# LowVBoard_01.net
KiCad netlist of a schematic drawn in EAGLE
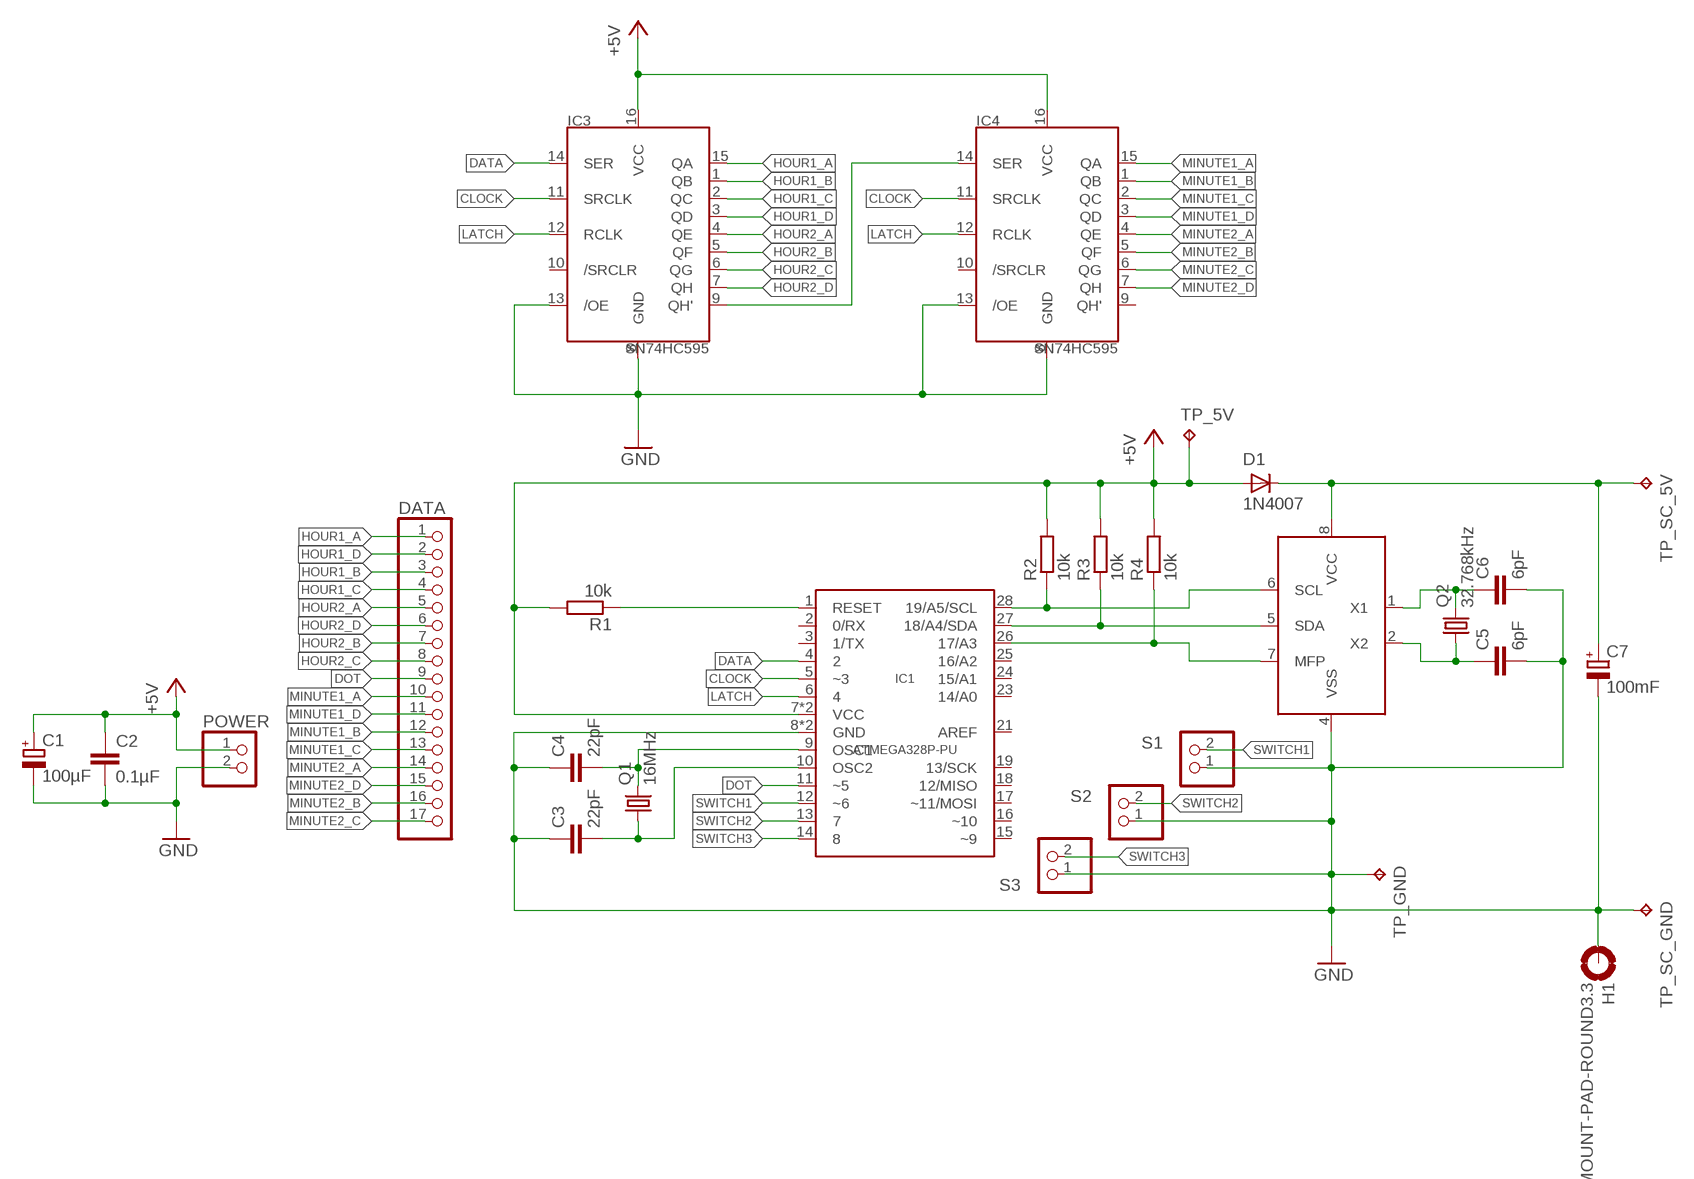
[diagram p0: schematic, sheet 1]

(export (version "E")
  (design (tool "Eeschema 10.0.6"))
  (components
    (comp (ref "C1")
      (value "100µF")
      (footprint "eagle-import:E2-5")
      (libsource (lib "eagle-import") (part "CPOL-EUE2-5"))
    )
    (comp (ref "C2")
      (value "0.1µF")
      (footprint "eagle-import:C025-024X044")
      (libsource (lib "eagle-import") (part "C-EU025-024X044"))
    )
    (comp (ref "C3")
      (value "22pF")
      (footprint "eagle-import:C025-024X044")
      (libsource (lib "eagle-import") (part "C-EU025-024X044"))
    )
    (comp (ref "C4")
      (value "22pF")
      (footprint "eagle-import:C025-024X044")
      (libsource (lib "eagle-import") (part "C-EU025-024X044"))
    )
    (comp (ref "C5")
      (value "6pF")
      (footprint "eagle-import:C025-024X044")
      (libsource (lib "eagle-import") (part "C-EU025-024X044"))
    )
    (comp (ref "C6")
      (value "6pF")
      (footprint "eagle-import:C025-024X044")
      (libsource (lib "eagle-import") (part "C-EU025-024X044"))
    )
    (comp (ref "C7")
      (value "100mF")
      (footprint "eagle-import:SUPERCAP-11.5")
      (libsource (lib "eagle-import") (part "FTW0H104ZF"))
    )
    (comp (ref "D1")
      (value "1N4007")
      (footprint "eagle-import:DO41-7.6")
      (libsource (lib "eagle-import") (part "1N4007"))
    )
    (comp (ref "DATA")
      (value "PINHD-1X17")
      (footprint "eagle-import:1X17")
      (libsource (lib "eagle-import") (part "PINHD-1X17"))
    )
    (comp (ref "H1")
      (value "MOUNT-PAD-ROUND3.3")
      (footprint "eagle-import:3,3-PAD")
      (libsource (lib "eagle-import") (part "MOUNT-PAD-ROUND3.3"))
    )
    (comp (ref "IC1")
      (value "ATMEGA328P-PU")
      (footprint "eagle-import:DIP28")
      (libsource (lib "eagle-import") (part "ATMEGA328P-PU"))
    )
    (comp (ref "IC2")
      (value "MCP7940M")
      (footprint "eagle-import:DIL8")
      (libsource (lib "eagle-import") (part "MCP7940M-I/P"))
    )
    (comp (ref "IC3")
      (value "SN74HC595")
      (footprint "eagle-import:DIL16")
      (libsource (lib "eagle-import") (part "SN74HC595"))
    )
    (comp (ref "IC4")
      (value "SN74HC595")
      (footprint "eagle-import:DIL16")
      (libsource (lib "eagle-import") (part "SN74HC595"))
    )
    (comp (ref "POWER")
      (value "PINHD-1X2")
      (footprint "eagle-import:1X02")
      (libsource (lib "eagle-import") (part "PINHD-1X2"))
    )
    (comp (ref "Q1")
      (value "16MHz")
      (footprint "eagle-import:HC49_S")
      (libsource (lib "eagle-import") (part "CRYSTALHC49S"))
    )
    (comp (ref "Q2")
      (value "32.768kHz")
      (footprint "eagle-import:CFS-206")
      (libsource (lib "eagle-import") (part "CFS-206"))
    )
    (comp (ref "R1")
      (value "10k")
      (footprint "eagle-import:0207_7")
      (libsource (lib "eagle-import") (part "R-EU_0207/7"))
    )
    (comp (ref "R2")
      (value "10k")
      (footprint "eagle-import:0207_7")
      (libsource (lib "eagle-import") (part "R-EU_0207/7"))
    )
    (comp (ref "R3")
      (value "10k")
      (footprint "eagle-import:0207_7")
      (libsource (lib "eagle-import") (part "R-EU_0207/7"))
    )
    (comp (ref "R4")
      (value "10k")
      (footprint "eagle-import:0207_7")
      (libsource (lib "eagle-import") (part "R-EU_0207/7"))
    )
    (comp (ref "S1")
      (value "PINHD-1X2/90")
      (footprint "eagle-import:1X02_90")
      (libsource (lib "eagle-import") (part "PINHD-1X2/90"))
    )
    (comp (ref "S2")
      (value "PINHD-1X2/90")
      (footprint "eagle-import:1X02_90")
      (libsource (lib "eagle-import") (part "PINHD-1X2/90"))
    )
    (comp (ref "S3")
      (value "PINHD-1X2/90")
      (footprint "eagle-import:1X02_90")
      (libsource (lib "eagle-import") (part "PINHD-1X2/90"))
    )
    (comp (ref "TP_5V")
      (value "TPPAD1-13")
      (footprint "eagle-import:P1-13")
      (libsource (lib "eagle-import") (part "TPPAD1-13"))
    )
    (comp (ref "TP_GND")
      (value "TPPAD1-13")
      (footprint "eagle-import:P1-13")
      (libsource (lib "eagle-import") (part "TPPAD1-13"))
    )
    (comp (ref "TP_SC_5V")
      (value "TPPAD1-13")
      (footprint "eagle-import:P1-13")
      (libsource (lib "eagle-import") (part "TPPAD1-13"))
    )
    (comp (ref "TP_SC_GND")
      (value "TPPAD1-13")
      (footprint "eagle-import:P1-13")
      (libsource (lib "eagle-import") (part "TPPAD1-13"))
    )
  )
  (nets
    (net (code "1") (name "+5V") (class "Default")
      (node (ref "C1") (pin "+") (pinfunction "+_+") (pintype "passive"))
      (node (ref "C2") (pin "1") (pinfunction "1_1") (pintype "passive"))
      (node (ref "D1") (pin "A") (pinfunction "A_A") (pintype "passive"))
      (node (ref "IC1") (pin "20") (pinfunction "VCC_20") (pintype "bidirectional"))
      (node (ref "IC1") (pin "7") (pinfunction "VCC_7") (pintype "bidirectional"))
      (node (ref "IC3") (pin "16") (pinfunction "VCC_16") (pintype "bidirectional"))
      (node (ref "IC4") (pin "16") (pinfunction "VCC_16") (pintype "bidirectional"))
      (node (ref "POWER") (pin "1") (pinfunction "1_1") (pintype "passive"))
      (node (ref "R1") (pin "2") (pinfunction "2_2") (pintype "passive"))
      (node (ref "R2") (pin "2") (pinfunction "2_2") (pintype "passive"))
      (node (ref "R3") (pin "2") (pinfunction "2_2") (pintype "passive"))
      (node (ref "R4") (pin "2") (pinfunction "2_2") (pintype "passive"))
      (node (ref "TP_5V") (pin "TP") (pinfunction "TP_TP") (pintype "input"))
    )
    (net (code "2") (name "CLOCK") (class "Default")
      (node (ref "IC1") (pin "5") (pinfunction "~{3}_5") (pintype "bidirectional"))
      (node (ref "IC3") (pin "11") (pinfunction "SRCLK_11") (pintype "bidirectional"))
      (node (ref "IC4") (pin "11") (pinfunction "SRCLK_11") (pintype "bidirectional"))
    )
    (net (code "3") (name "DATA") (class "Default")
      (node (ref "IC1") (pin "4") (pinfunction "2_4") (pintype "bidirectional"))
      (node (ref "IC3") (pin "14") (pinfunction "SER_14") (pintype "bidirectional"))
    )
    (net (code "4") (name "DOT") (class "Default")
      (node (ref "DATA") (pin "9") (pinfunction "9_9") (pintype "passive"))
      (node (ref "IC1") (pin "11") (pinfunction "~{5}_11") (pintype "bidirectional"))
    )
    (net (code "5") (name "GND") (class "Default")
      (node (ref "C1") (pin "-") (pinfunction "-_-") (pintype "passive"))
      (node (ref "C2") (pin "2") (pinfunction "2_2") (pintype "passive"))
      (node (ref "C3") (pin "1") (pinfunction "1_1") (pintype "passive"))
      (node (ref "C4") (pin "1") (pinfunction "1_1") (pintype "passive"))
      (node (ref "C5") (pin "2") (pinfunction "2_2") (pintype "passive"))
      (node (ref "C6") (pin "2") (pinfunction "2_2") (pintype "passive"))
      (node (ref "C7") (pin "-") (pinfunction "-_-") (pintype "passive"))
      (node (ref "H1") (pin "B3,3") (pinfunction "MOUNT_B3,3") (pintype "passive"))
      (node (ref "IC1") (pin "22") (pinfunction "GND_22") (pintype "bidirectional"))
      (node (ref "IC1") (pin "8") (pinfunction "GND_8") (pintype "bidirectional"))
      (node (ref "IC2") (pin "4") (pinfunction "VSS_4") (pintype "bidirectional"))
      (node (ref "IC3") (pin "13") (pinfunction "/OE_13") (pintype "bidirectional"))
      (node (ref "IC3") (pin "8") (pinfunction "GND_8") (pintype "bidirectional"))
      (node (ref "IC4") (pin "13") (pinfunction "/OE_13") (pintype "bidirectional"))
      (node (ref "IC4") (pin "8") (pinfunction "GND_8") (pintype "bidirectional"))
      (node (ref "POWER") (pin "2") (pinfunction "2_2") (pintype "passive"))
      (node (ref "S1") (pin "1") (pinfunction "1_1") (pintype "passive"))
      (node (ref "S2") (pin "1") (pinfunction "1_1") (pintype "passive"))
      (node (ref "S3") (pin "1") (pinfunction "1_1") (pintype "passive"))
      (node (ref "TP_GND") (pin "TP") (pinfunction "TP_TP") (pintype "input"))
      (node (ref "TP_SC_GND") (pin "TP") (pinfunction "TP_TP") (pintype "input"))
    )
    (net (code "6") (name "HOUR1_A") (class "Default")
      (node (ref "DATA") (pin "1") (pinfunction "1_1") (pintype "passive"))
      (node (ref "IC3") (pin "15") (pinfunction "QA_15") (pintype "bidirectional"))
    )
    (net (code "7") (name "HOUR1_B") (class "Default")
      (node (ref "DATA") (pin "3") (pinfunction "3_3") (pintype "passive"))
      (node (ref "IC3") (pin "1") (pinfunction "QB_1") (pintype "bidirectional"))
    )
    (net (code "8") (name "HOUR1_C") (class "Default")
      (node (ref "DATA") (pin "4") (pinfunction "4_4") (pintype "passive"))
      (node (ref "IC3") (pin "2") (pinfunction "QC_2") (pintype "bidirectional"))
    )
    (net (code "9") (name "HOUR1_D") (class "Default")
      (node (ref "DATA") (pin "2") (pinfunction "2_2") (pintype "passive"))
      (node (ref "IC3") (pin "3") (pinfunction "QD_3") (pintype "bidirectional"))
    )
    (net (code "10") (name "HOUR2_A") (class "Default")
      (node (ref "DATA") (pin "5") (pinfunction "5_5") (pintype "passive"))
      (node (ref "IC3") (pin "4") (pinfunction "QE_4") (pintype "bidirectional"))
    )
    (net (code "11") (name "HOUR2_B") (class "Default")
      (node (ref "DATA") (pin "7") (pinfunction "7_7") (pintype "passive"))
      (node (ref "IC3") (pin "5") (pinfunction "QF_5") (pintype "bidirectional"))
    )
    (net (code "12") (name "HOUR2_C") (class "Default")
      (node (ref "DATA") (pin "8") (pinfunction "8_8") (pintype "passive"))
      (node (ref "IC3") (pin "6") (pinfunction "QG_6") (pintype "bidirectional"))
    )
    (net (code "13") (name "HOUR2_D") (class "Default")
      (node (ref "DATA") (pin "6") (pinfunction "6_6") (pintype "passive"))
      (node (ref "IC3") (pin "7") (pinfunction "QH_7") (pintype "bidirectional"))
    )
    (net (code "14") (name "LATCH") (class "Default")
      (node (ref "IC1") (pin "6") (pinfunction "4_6") (pintype "bidirectional"))
      (node (ref "IC3") (pin "12") (pinfunction "RCLK_12") (pintype "bidirectional"))
      (node (ref "IC4") (pin "12") (pinfunction "RCLK_12") (pintype "bidirectional"))
    )
    (net (code "15") (name "MINUTE1_A") (class "Default")
      (node (ref "DATA") (pin "10") (pinfunction "10_10") (pintype "passive"))
      (node (ref "IC4") (pin "15") (pinfunction "QA_15") (pintype "bidirectional"))
    )
    (net (code "16") (name "MINUTE1_B") (class "Default")
      (node (ref "DATA") (pin "12") (pinfunction "12_12") (pintype "passive"))
      (node (ref "IC4") (pin "1") (pinfunction "QB_1") (pintype "bidirectional"))
    )
    (net (code "17") (name "MINUTE1_C") (class "Default")
      (node (ref "DATA") (pin "13") (pinfunction "13_13") (pintype "passive"))
      (node (ref "IC4") (pin "2") (pinfunction "QC_2") (pintype "bidirectional"))
    )
    (net (code "18") (name "MINUTE1_D") (class "Default")
      (node (ref "DATA") (pin "11") (pinfunction "11_11") (pintype "passive"))
      (node (ref "IC4") (pin "3") (pinfunction "QD_3") (pintype "bidirectional"))
    )
    (net (code "19") (name "MINUTE2_A") (class "Default")
      (node (ref "DATA") (pin "14") (pinfunction "14_14") (pintype "passive"))
      (node (ref "IC4") (pin "4") (pinfunction "QE_4") (pintype "bidirectional"))
    )
    (net (code "20") (name "MINUTE2_B") (class "Default")
      (node (ref "DATA") (pin "16") (pinfunction "16_16") (pintype "passive"))
      (node (ref "IC4") (pin "5") (pinfunction "QF_5") (pintype "bidirectional"))
    )
    (net (code "21") (name "MINUTE2_C") (class "Default")
      (node (ref "DATA") (pin "17") (pinfunction "17_17") (pintype "passive"))
      (node (ref "IC4") (pin "6") (pinfunction "QG_6") (pintype "bidirectional"))
    )
    (net (code "22") (name "MINUTE2_D") (class "Default")
      (node (ref "DATA") (pin "15") (pinfunction "15_15") (pintype "passive"))
      (node (ref "IC4") (pin "7") (pinfunction "QH_7") (pintype "bidirectional"))
    )
    (net (code "23") (name "Net-(IC1-17{slash}A3)") (class "Default")
      (node (ref "IC1") (pin "26") (pinfunction "17/A3_26") (pintype "bidirectional"))
      (node (ref "IC2") (pin "7") (pinfunction "MFP_7") (pintype "bidirectional"))
      (node (ref "R4") (pin "1") (pinfunction "1_1") (pintype "passive"))
    )
    (net (code "24") (name "Net-(IC1-18{slash}A4{slash}SDA)") (class "Default")
      (node (ref "IC1") (pin "27") (pinfunction "18/A4/SDA_27") (pintype "bidirectional"))
      (node (ref "IC2") (pin "5") (pinfunction "SDA_5") (pintype "bidirectional"))
      (node (ref "R3") (pin "1") (pinfunction "1_1") (pintype "passive"))
    )
    (net (code "25") (name "Net-(IC1-19{slash}A5{slash}SCL)") (class "Default")
      (node (ref "IC1") (pin "28") (pinfunction "19/A5/SCL_28") (pintype "bidirectional"))
      (node (ref "IC2") (pin "6") (pinfunction "SCL_6") (pintype "bidirectional"))
      (node (ref "R2") (pin "1") (pinfunction "1_1") (pintype "passive"))
    )
    (net (code "26") (name "Net-(IC1-OSC1)") (class "Default")
      (node (ref "C4") (pin "2") (pinfunction "2_2") (pintype "passive"))
      (node (ref "IC1") (pin "9") (pinfunction "OSC1_9") (pintype "bidirectional"))
      (node (ref "Q1") (pin "2") (pinfunction "2_2") (pintype "passive"))
    )
    (net (code "27") (name "Net-(IC1-OSC2)") (class "Default")
      (node (ref "C3") (pin "2") (pinfunction "2_2") (pintype "passive"))
      (node (ref "IC1") (pin "10") (pinfunction "OSC2_10") (pintype "bidirectional"))
      (node (ref "Q1") (pin "1") (pinfunction "1_1") (pintype "passive"))
    )
    (net (code "28") (name "Net-(IC1-RESET)") (class "Default")
      (node (ref "IC1") (pin "1") (pinfunction "RESET_1") (pintype "bidirectional"))
      (node (ref "R1") (pin "1") (pinfunction "1_1") (pintype "passive"))
    )
    (net (code "29") (name "Net-(IC2-VCC)") (class "Default")
      (node (ref "C7") (pin "+") (pinfunction "+_+") (pintype "passive"))
      (node (ref "D1") (pin "C") (pinfunction "C_C") (pintype "passive"))
      (node (ref "IC2") (pin "8") (pinfunction "VCC_8") (pintype "bidirectional"))
      (node (ref "TP_SC_5V") (pin "TP") (pinfunction "TP_TP") (pintype "input"))
    )
    (net (code "30") (name "Net-(IC2-X1)") (class "Default")
      (node (ref "C6") (pin "1") (pinfunction "1_1") (pintype "passive"))
      (node (ref "IC2") (pin "1") (pinfunction "X1_1") (pintype "bidirectional"))
      (node (ref "Q2") (pin "P$2") (pinfunction "2_P$2") (pintype "passive"))
    )
    (net (code "31") (name "Net-(IC2-X2)") (class "Default")
      (node (ref "C5") (pin "1") (pinfunction "1_1") (pintype "passive"))
      (node (ref "IC2") (pin "2") (pinfunction "X2_2") (pintype "bidirectional"))
      (node (ref "Q2") (pin "P$1") (pinfunction "1_P$1") (pintype "passive"))
    )
    (net (code "32") (name "Net-(IC3-QH')") (class "Default")
      (node (ref "IC3") (pin "9") (pinfunction "QH'_9") (pintype "bidirectional"))
      (node (ref "IC4") (pin "14") (pinfunction "SER_14") (pintype "bidirectional"))
    )
    (net (code "33") (name "SWITCH1") (class "Default")
      (node (ref "IC1") (pin "12") (pinfunction "~{6}_12") (pintype "bidirectional"))
      (node (ref "S1") (pin "2") (pinfunction "2_2") (pintype "passive"))
    )
    (net (code "34") (name "SWITCH2") (class "Default")
      (node (ref "IC1") (pin "13") (pinfunction "7_13") (pintype "bidirectional"))
      (node (ref "S2") (pin "2") (pinfunction "2_2") (pintype "passive"))
    )
    (net (code "35") (name "SWITCH3") (class "Default")
      (node (ref "IC1") (pin "14") (pinfunction "8_14") (pintype "bidirectional"))
      (node (ref "S3") (pin "2") (pinfunction "2_2") (pintype "passive"))
    )
    (net (code "36") (name "unconnected-(IC1-0{slash}RX-Pad2)") (class "Default")
      (node (ref "IC1") (pin "2") (pinfunction "0/RX_2") (pintype "bidirectional"))
    )
    (net (code "37") (name "unconnected-(IC1-1{slash}TX-Pad3)") (class "Default")
      (node (ref "IC1") (pin "3") (pinfunction "1/TX_3") (pintype "bidirectional"))
    )
    (net (code "38") (name "unconnected-(IC1-12{slash}MISO-Pad18)") (class "Default")
      (node (ref "IC1") (pin "18") (pinfunction "12/MISO_18") (pintype "bidirectional"))
    )
    (net (code "39") (name "unconnected-(IC1-13{slash}SCK-Pad19)") (class "Default")
      (node (ref "IC1") (pin "19") (pinfunction "13/SCK_19") (pintype "bidirectional"))
    )
    (net (code "40") (name "unconnected-(IC1-14{slash}A0-Pad23)") (class "Default")
      (node (ref "IC1") (pin "23") (pinfunction "14/A0_23") (pintype "bidirectional"))
    )
    (net (code "41") (name "unconnected-(IC1-15{slash}A1-Pad24)") (class "Default")
      (node (ref "IC1") (pin "24") (pinfunction "15/A1_24") (pintype "bidirectional"))
    )
    (net (code "42") (name "unconnected-(IC1-16{slash}A2-Pad25)") (class "Default")
      (node (ref "IC1") (pin "25") (pinfunction "16/A2_25") (pintype "bidirectional"))
    )
    (net (code "43") (name "unconnected-(IC1-AREF-Pad21)") (class "Default")
      (node (ref "IC1") (pin "21") (pinfunction "AREF_21") (pintype "bidirectional"))
    )
    (net (code "44") (name "unconnected-(IC1-~{9}-Pad15)") (class "Default")
      (node (ref "IC1") (pin "15") (pinfunction "~{9}_15") (pintype "bidirectional"))
    )
    (net (code "45") (name "unconnected-(IC1-~{10}-Pad16)") (class "Default")
      (node (ref "IC1") (pin "16") (pinfunction "~{10}_16") (pintype "bidirectional"))
    )
    (net (code "46") (name "unconnected-(IC1-~{11{slash}MOSI}-Pad17)") (class "Default")
      (node (ref "IC1") (pin "17") (pinfunction "~{11/MOSI}_17") (pintype "bidirectional"))
    )
    (net (code "47") (name "unconnected-(IC3-{slash}SRCLR-Pad10)") (class "Default")
      (node (ref "IC3") (pin "10") (pinfunction "/SRCLR_10") (pintype "bidirectional"))
    )
    (net (code "48") (name "unconnected-(IC4-QH'-Pad9)") (class "Default")
      (node (ref "IC4") (pin "9") (pinfunction "QH'_9") (pintype "bidirectional"))
    )
    (net (code "49") (name "unconnected-(IC4-{slash}SRCLR-Pad10)") (class "Default")
      (node (ref "IC4") (pin "10") (pinfunction "/SRCLR_10") (pintype "bidirectional"))
    )
  )
)
